# Shruthi-Analog-LP2Delay-v02.net
KiCad netlist of a schematic drawn in EAGLE
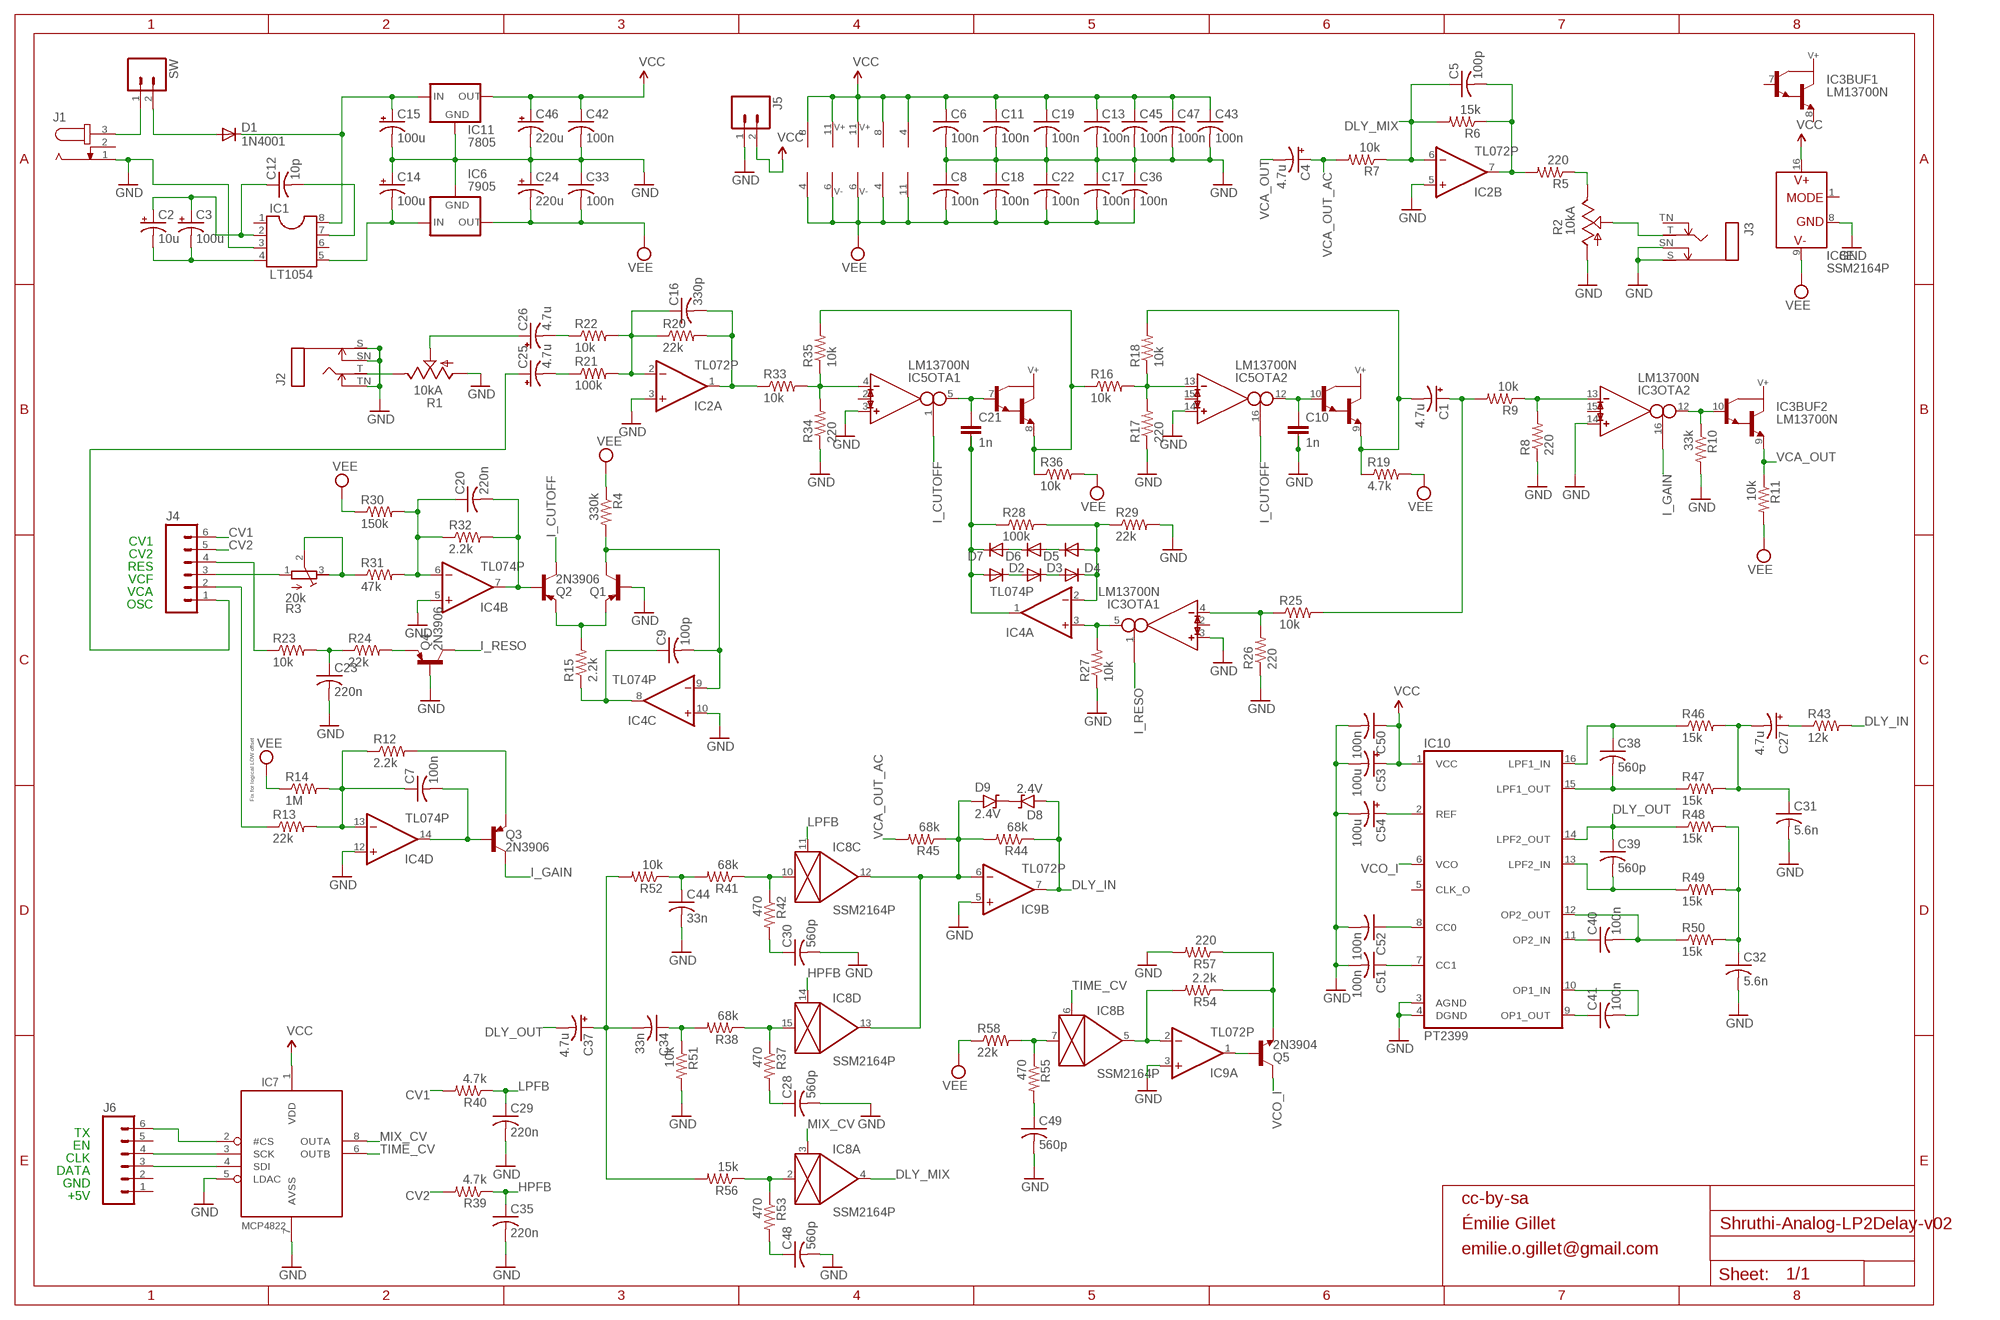
[diagram p0: schematic, sheet 1]

(export (version "E")
  (design (tool "Eeschema 10.0.6"))
  (components
    (comp (ref "C1")
      (value "4.7u")
      (footprint "eagle-import:E2,5-6")
      (libsource (lib "eagle-import") (part "CPOL-USE2.5-6"))
    )
    (comp (ref "C2")
      (value "10u")
      (footprint "eagle-import:E2,5-5")
      (libsource (lib "eagle-import") (part "CPOL-USE2.5-5"))
    )
    (comp (ref "C3")
      (value "100u")
      (footprint "eagle-import:E2,5-6")
      (libsource (lib "eagle-import") (part "CPOL-USE2.5-6"))
    )
    (comp (ref "C4")
      (value "4.7u")
      (footprint "eagle-import:E2,5-6")
      (libsource (lib "eagle-import") (part "CPOL-USE2.5-6"))
    )
    (comp (ref "C5")
      (value "100p")
      (footprint "eagle-import:C025-025X050")
      (libsource (lib "eagle-import") (part "C-US025-025X050"))
    )
    (comp (ref "C6")
      (value "100n")
      (footprint "eagle-import:C025-025X050")
      (libsource (lib "eagle-import") (part "C-US025-025X050"))
    )
    (comp (ref "C7")
      (value "100n")
      (footprint "eagle-import:C025-025X050")
      (libsource (lib "eagle-import") (part "C-US025-025X050"))
    )
    (comp (ref "C8")
      (value "100n")
      (footprint "eagle-import:C025-025X050")
      (libsource (lib "eagle-import") (part "C-US025-025X050"))
    )
    (comp (ref "C9")
      (value "100p")
      (footprint "eagle-import:C025-025X050")
      (libsource (lib "eagle-import") (part "C-US025-025X050"))
    )
    (comp (ref "C10")
      (value "1n")
      (footprint "eagle-import:C2.5_5-2")
      (libsource (lib "eagle-import") (part "C-2.5-5/2"))
    )
    (comp (ref "C11")
      (value "100n")
      (footprint "eagle-import:C025-025X050")
      (libsource (lib "eagle-import") (part "C-US025-025X050"))
    )
    (comp (ref "C12")
      (value "10p")
      (footprint "eagle-import:C025-025X050")
      (libsource (lib "eagle-import") (part "C-US025-025X050"))
    )
    (comp (ref "C13")
      (value "100n")
      (footprint "eagle-import:C025-025X050")
      (libsource (lib "eagle-import") (part "C-US025-025X050"))
    )
    (comp (ref "C14")
      (value "100u")
      (footprint "eagle-import:E2,5-7")
      (libsource (lib "eagle-import") (part "CPOL-USE2.5-7"))
    )
    (comp (ref "C15")
      (value "100u")
      (footprint "eagle-import:E2,5-7")
      (libsource (lib "eagle-import") (part "CPOL-USE2.5-7"))
    )
    (comp (ref "C16")
      (value "330p")
      (footprint "eagle-import:C025-025X050")
      (libsource (lib "eagle-import") (part "C-US025-025X050"))
    )
    (comp (ref "C17")
      (value "100n")
      (footprint "eagle-import:C025-025X050")
      (libsource (lib "eagle-import") (part "C-US025-025X050"))
    )
    (comp (ref "C18")
      (value "100n")
      (footprint "eagle-import:C025-025X050")
      (libsource (lib "eagle-import") (part "C-US025-025X050"))
    )
    (comp (ref "C19")
      (value "100n")
      (footprint "eagle-import:C025-025X050")
      (libsource (lib "eagle-import") (part "C-US025-025X050"))
    )
    (comp (ref "C20")
      (value "220n")
      (footprint "eagle-import:C025-025X050")
      (libsource (lib "eagle-import") (part "C-US025-025X050"))
    )
    (comp (ref "C21")
      (value "1n")
      (footprint "eagle-import:C2.5_5-2")
      (libsource (lib "eagle-import") (part "C-2.5-5/2"))
    )
    (comp (ref "C22")
      (value "100n")
      (footprint "eagle-import:C025-025X050")
      (libsource (lib "eagle-import") (part "C-US025-025X050"))
    )
    (comp (ref "C23")
      (value "220n")
      (footprint "eagle-import:C025-025X050")
      (libsource (lib "eagle-import") (part "C-US025-025X050"))
    )
    (comp (ref "C24")
      (value "220u")
      (footprint "eagle-import:E5-10,5")
      (libsource (lib "eagle-import") (part "CPOL-USE5-10.5"))
    )
    (comp (ref "C25")
      (value "4.7u")
      (footprint "eagle-import:E2,5-6")
      (libsource (lib "eagle-import") (part "CPOL-USE2.5-6"))
    )
    (comp (ref "C26")
      (value "4.7u")
      (footprint "eagle-import:E2,5-6")
      (libsource (lib "eagle-import") (part "CPOL-USE2.5-6"))
    )
    (comp (ref "C27")
      (value "4.7u")
      (footprint "eagle-import:E2,5-6")
      (libsource (lib "eagle-import") (part "CPOL-USE2.5-6"))
    )
    (comp (ref "C28")
      (value "560p")
      (footprint "eagle-import:C025-025X050")
      (libsource (lib "eagle-import") (part "C-US025-025X050"))
    )
    (comp (ref "C29")
      (value "220n")
      (footprint "eagle-import:C025-025X050")
      (libsource (lib "eagle-import") (part "C-US025-025X050"))
    )
    (comp (ref "C30")
      (value "560p")
      (footprint "eagle-import:C025-025X050")
      (libsource (lib "eagle-import") (part "C-US025-025X050"))
    )
    (comp (ref "C31")
      (value "5.6n")
      (footprint "eagle-import:C025-025X050")
      (libsource (lib "eagle-import") (part "C-US025-025X050"))
    )
    (comp (ref "C32")
      (value "5.6n")
      (footprint "eagle-import:C025-025X050")
      (libsource (lib "eagle-import") (part "C-US025-025X050"))
    )
    (comp (ref "C33")
      (value "100n")
      (footprint "eagle-import:C025-025X050")
      (libsource (lib "eagle-import") (part "C-US025-025X050"))
    )
    (comp (ref "C34")
      (value "33n")
      (footprint "eagle-import:C050-025X075")
      (libsource (lib "eagle-import") (part "C-US050-025X075"))
    )
    (comp (ref "C35")
      (value "220n")
      (footprint "eagle-import:C025-025X050")
      (libsource (lib "eagle-import") (part "C-US025-025X050"))
    )
    (comp (ref "C36")
      (value "100n")
      (footprint "eagle-import:C025-025X050")
      (libsource (lib "eagle-import") (part "C-US025-025X050"))
    )
    (comp (ref "C37")
      (value "4.7u")
      (footprint "eagle-import:E2,5-6")
      (libsource (lib "eagle-import") (part "CPOL-USE2.5-6"))
    )
    (comp (ref "C38")
      (value "560p")
      (footprint "eagle-import:C025-025X050")
      (libsource (lib "eagle-import") (part "C-US025-025X050"))
    )
    (comp (ref "C39")
      (value "560p")
      (footprint "eagle-import:C025-025X050")
      (libsource (lib "eagle-import") (part "C-US025-025X050"))
    )
    (comp (ref "C40")
      (value "100n")
      (footprint "eagle-import:C025-025X050")
      (libsource (lib "eagle-import") (part "C-US025-025X050"))
    )
    (comp (ref "C41")
      (value "100n")
      (footprint "eagle-import:C025-025X050")
      (libsource (lib "eagle-import") (part "C-US025-025X050"))
    )
    (comp (ref "C42")
      (value "100n")
      (footprint "eagle-import:C025-025X050")
      (libsource (lib "eagle-import") (part "C-US025-025X050"))
    )
    (comp (ref "C43")
      (value "100n")
      (footprint "eagle-import:C025-025X050")
      (libsource (lib "eagle-import") (part "C-US025-025X050"))
    )
    (comp (ref "C44")
      (value "33n")
      (footprint "eagle-import:C050-025X075")
      (libsource (lib "eagle-import") (part "C-US050-025X075"))
    )
    (comp (ref "C45")
      (value "100n")
      (footprint "eagle-import:C025-025X050")
      (libsource (lib "eagle-import") (part "C-US025-025X050"))
    )
    (comp (ref "C46")
      (value "220u")
      (footprint "eagle-import:E5-10,5")
      (libsource (lib "eagle-import") (part "CPOL-USE5-10.5"))
    )
    (comp (ref "C47")
      (value "100n")
      (footprint "eagle-import:C025-025X050")
      (libsource (lib "eagle-import") (part "C-US025-025X050"))
    )
    (comp (ref "C48")
      (value "560p")
      (footprint "eagle-import:C025-025X050")
      (libsource (lib "eagle-import") (part "C-US025-025X050"))
    )
    (comp (ref "C49")
      (value "560p")
      (footprint "eagle-import:C025-025X050")
      (libsource (lib "eagle-import") (part "C-US025-025X050"))
    )
    (comp (ref "C50")
      (value "100n")
      (footprint "eagle-import:C025-025X050")
      (libsource (lib "eagle-import") (part "C-US025-025X050"))
    )
    (comp (ref "C51")
      (value "100n")
      (footprint "eagle-import:C025-025X050")
      (libsource (lib "eagle-import") (part "C-US025-025X050"))
    )
    (comp (ref "C52")
      (value "100n")
      (footprint "eagle-import:C025-025X050")
      (libsource (lib "eagle-import") (part "C-US025-025X050"))
    )
    (comp (ref "C53")
      (value "100u")
      (footprint "eagle-import:E2,5-7")
      (libsource (lib "eagle-import") (part "CPOL-USE2.5-7"))
    )
    (comp (ref "C54")
      (value "100u")
      (footprint "eagle-import:E2,5-7")
      (libsource (lib "eagle-import") (part "CPOL-USE2.5-7"))
    )
    (comp (ref "D1")
      (value "1N4001")
      (footprint "eagle-import:DO41-10")
      (libsource (lib "eagle-import") (part "1N4004"))
    )
    (comp (ref "D2")
      (value "DIODE-D-5")
      (footprint "eagle-import:D-5")
      (libsource (lib "eagle-import") (part "DIODE-D-5"))
    )
    (comp (ref "D3")
      (value "DIODE-D-5")
      (footprint "eagle-import:D-5")
      (libsource (lib "eagle-import") (part "DIODE-D-5"))
    )
    (comp (ref "D4")
      (value "DIODE-D-5")
      (footprint "eagle-import:D-5")
      (libsource (lib "eagle-import") (part "DIODE-D-5"))
    )
    (comp (ref "D5")
      (value "DIODE-D-5")
      (footprint "eagle-import:D-5")
      (libsource (lib "eagle-import") (part "DIODE-D-5"))
    )
    (comp (ref "D6")
      (value "DIODE-D-5")
      (footprint "eagle-import:D-5")
      (libsource (lib "eagle-import") (part "DIODE-D-5"))
    )
    (comp (ref "D7")
      (value "DIODE-D-5")
      (footprint "eagle-import:D-5")
      (libsource (lib "eagle-import") (part "DIODE-D-5"))
    )
    (comp (ref "D8")
      (value "2.4V")
      (footprint "eagle-import:D-5")
      (libsource (lib "eagle-import") (part "1N47XXDO35"))
    )
    (comp (ref "D9")
      (value "2.4V")
      (footprint "eagle-import:D-5")
      (libsource (lib "eagle-import") (part "1N47XXDO35"))
    )
    (comp (ref "IC1")
      (value "LT1054")
      (footprint "eagle-import:DIL08")
      (libsource (lib "eagle-import") (part "DIL8"))
    )
    (comp (ref "IC2")
      (value "TL072P")
      (footprint "eagle-import:DIL08")
      (libsource (lib "eagle-import") (part "TL072P"))
    )
    (comp (ref "IC3")
      (value "LM13700N")
      (footprint "eagle-import:DIL16")
      (libsource (lib "eagle-import") (part "LM13700N"))
    )
    (comp (ref "IC4")
      (value "TL074P")
      (footprint "eagle-import:DIL14")
      (libsource (lib "eagle-import") (part "TL084P"))
    )
    (comp (ref "IC5")
      (value "LM13700N")
      (footprint "eagle-import:DIL16")
      (libsource (lib "eagle-import") (part "LM13700N"))
    )
    (comp (ref "IC6")
      (value "7905")
      (footprint "eagle-import:79XXS")
      (libsource (lib "eagle-import") (part "79XXS"))
    )
    (comp (ref "IC7")
      (value "MCP4822")
      (footprint "eagle-import:DIL08")
      (libsource (lib "eagle-import") (part "MCP4822"))
    )
    (comp (ref "IC8")
      (value "SSM2164P")
      (footprint "eagle-import:DIL16")
      (libsource (lib "eagle-import") (part "SSM2164P"))
    )
    (comp (ref "IC9")
      (value "TL072P")
      (footprint "eagle-import:DIL08")
      (libsource (lib "eagle-import") (part "TL072P"))
    )
    (comp (ref "IC10")
      (value "PT2399")
      (footprint "eagle-import:DIL16")
      (libsource (lib "eagle-import") (part "PT2399"))
    )
    (comp (ref "IC11")
      (value "7805")
      (footprint "eagle-import:78XXS")
      (libsource (lib "eagle-import") (part "78XXS"))
    )
    (comp (ref "J1")
      (value "JACK-PLUG2")
      (footprint "eagle-import:SPC4078_BIG_HOLES")
      (libsource (lib "eagle-import") (part "JACK-PLUG2"))
    )
    (comp (ref "J2")
      (value "MONOSWS")
      (footprint "eagle-import:NMJ4HC-S")
      (libsource (lib "eagle-import") (part "MONOSWS"))
    )
    (comp (ref "J3")
      (value "MONOSWS")
      (footprint "eagle-import:NMJ4HC-S")
      (libsource (lib "eagle-import") (part "MONOSWS"))
    )
    (comp (ref "J4")
      (value "M06SIP")
      (footprint "eagle-import:1X06")
      (libsource (lib "eagle-import") (part "M06SIP"))
    )
    (comp (ref "J5")
      (value "M02PTH")
      (footprint "eagle-import:1X02")
      (libsource (lib "eagle-import") (part "M02PTH"))
    )
    (comp (ref "J6")
      (value "M06SIP")
      (footprint "eagle-import:1X06")
      (libsource (lib "eagle-import") (part "M06SIP"))
    )
    (comp (ref "Q1")
      (value "2N3906")
      (footprint "eagle-import:TO92-")
      (libsource (lib "eagle-import") (part "2N3906-"))
    )
    (comp (ref "Q2")
      (value "2N3906")
      (footprint "eagle-import:TO92-")
      (libsource (lib "eagle-import") (part "2N3906-"))
    )
    (comp (ref "Q3")
      (value "2N3906")
      (footprint "eagle-import:TO92-")
      (libsource (lib "eagle-import") (part "2N3906-"))
    )
    (comp (ref "Q4")
      (value "2N3906")
      (footprint "eagle-import:TO92-")
      (libsource (lib "eagle-import") (part "2N3906-"))
    )
    (comp (ref "Q5")
      (value "2N3904")
      (footprint "eagle-import:TO92-")
      (libsource (lib "eagle-import") (part "2N3904"))
    )
    (comp (ref "R1")
      (value "10kA")
      (footprint "eagle-import:CABLE_POT_6MM")
      (libsource (lib "eagle-import") (part "POT_USCABLED"))
    )
    (comp (ref "R2")
      (value "10kA")
      (footprint "eagle-import:CABLE_POT_6MM")
      (libsource (lib "eagle-import") (part "POT_USCABLED"))
    )
    (comp (ref "R3")
      (value "20k")
      (footprint "eagle-import:RTRIM3296X")
      (libsource (lib "eagle-import") (part "R-TRIMM3296X"))
    )
    (comp (ref "R4")
      (value "330k")
      (footprint "eagle-import:0204_7")
      (libsource (lib "eagle-import") (part "R-US_0204/7"))
    )
    (comp (ref "R5")
      (value "220")
      (footprint "eagle-import:0204_7")
      (libsource (lib "eagle-import") (part "R-US_0204/7"))
    )
    (comp (ref "R6")
      (value "15k")
      (footprint "eagle-import:0204_7")
      (libsource (lib "eagle-import") (part "R-US_0204/7"))
    )
    (comp (ref "R7")
      (value "10k")
      (footprint "eagle-import:0204_7")
      (libsource (lib "eagle-import") (part "R-US_0204/7"))
    )
    (comp (ref "R8")
      (value "220")
      (footprint "eagle-import:0204_7")
      (libsource (lib "eagle-import") (part "R-US_0204/7"))
    )
    (comp (ref "R9")
      (value "10k")
      (footprint "eagle-import:0204_7")
      (libsource (lib "eagle-import") (part "R-US_0204/7"))
    )
    (comp (ref "R10")
      (value "33k")
      (footprint "eagle-import:0204_7")
      (libsource (lib "eagle-import") (part "R-US_0204/7"))
    )
    (comp (ref "R11")
      (value "10k")
      (footprint "eagle-import:0204_7")
      (libsource (lib "eagle-import") (part "R-US_0204/7"))
    )
    (comp (ref "R12")
      (value "2.2k")
      (footprint "eagle-import:0204_7")
      (libsource (lib "eagle-import") (part "R-US_0204/7"))
    )
    (comp (ref "R13")
      (value "22k")
      (footprint "eagle-import:0204_7")
      (libsource (lib "eagle-import") (part "R-US_0204/7"))
    )
    (comp (ref "R14")
      (value "1M")
      (footprint "eagle-import:0204_7")
      (libsource (lib "eagle-import") (part "R-US_0204/7"))
    )
    (comp (ref "R15")
      (value "2.2k")
      (footprint "eagle-import:0204_7")
      (libsource (lib "eagle-import") (part "R-US_0204/7"))
    )
    (comp (ref "R16")
      (value "10k")
      (footprint "eagle-import:0204_7")
      (libsource (lib "eagle-import") (part "R-US_0204/7"))
    )
    (comp (ref "R17")
      (value "220")
      (footprint "eagle-import:0204_7")
      (libsource (lib "eagle-import") (part "R-US_0204/7"))
    )
    (comp (ref "R18")
      (value "10k")
      (footprint "eagle-import:0204_7")
      (libsource (lib "eagle-import") (part "R-US_0204/7"))
    )
    (comp (ref "R19")
      (value "4.7k")
      (footprint "eagle-import:0204_7")
      (libsource (lib "eagle-import") (part "R-US_0204/7"))
    )
    (comp (ref "R20")
      (value "22k")
      (footprint "eagle-import:0204_7")
      (libsource (lib "eagle-import") (part "R-US_0204/7"))
    )
    (comp (ref "R21")
      (value "100k")
      (footprint "eagle-import:0204_7")
      (libsource (lib "eagle-import") (part "R-US_0204/7"))
    )
    (comp (ref "R22")
      (value "10k")
      (footprint "eagle-import:0204_7")
      (libsource (lib "eagle-import") (part "R-US_0204/7"))
    )
    (comp (ref "R23")
      (value "10k")
      (footprint "eagle-import:0204_7")
      (libsource (lib "eagle-import") (part "R-US_0204/7"))
    )
    (comp (ref "R24")
      (value "22k")
      (footprint "eagle-import:0204_7")
      (libsource (lib "eagle-import") (part "R-US_0204/7"))
    )
    (comp (ref "R25")
      (value "10k")
      (footprint "eagle-import:0204_7")
      (libsource (lib "eagle-import") (part "R-US_0204/7"))
    )
    (comp (ref "R26")
      (value "220")
      (footprint "eagle-import:0204_7")
      (libsource (lib "eagle-import") (part "R-US_0204/7"))
    )
    (comp (ref "R27")
      (value "10k")
      (footprint "eagle-import:0204_7")
      (libsource (lib "eagle-import") (part "R-US_0204/7"))
    )
    (comp (ref "R28")
      (value "100k")
      (footprint "eagle-import:0204_7")
      (libsource (lib "eagle-import") (part "R-US_0204/7"))
    )
    (comp (ref "R29")
      (value "22k")
      (footprint "eagle-import:0204_7")
      (libsource (lib "eagle-import") (part "R-US_0204/7"))
    )
    (comp (ref "R30")
      (value "150k")
      (footprint "eagle-import:0204_7")
      (libsource (lib "eagle-import") (part "R-US_0204/7"))
    )
    (comp (ref "R31")
      (value "47k")
      (footprint "eagle-import:0204_7")
      (libsource (lib "eagle-import") (part "R-US_0204/7"))
    )
    (comp (ref "R32")
      (value "2.2k")
      (footprint "eagle-import:0204_7")
      (libsource (lib "eagle-import") (part "R-US_0204/7"))
    )
    (comp (ref "R33")
      (value "10k")
      (footprint "eagle-import:0204_7")
      (libsource (lib "eagle-import") (part "R-US_0204/7"))
    )
    (comp (ref "R34")
      (value "220")
      (footprint "eagle-import:0204_7")
      (libsource (lib "eagle-import") (part "R-US_0204/7"))
    )
    (comp (ref "R35")
      (value "10k")
      (footprint "eagle-import:0204_7")
      (libsource (lib "eagle-import") (part "R-US_0204/7"))
    )
    (comp (ref "R36")
      (value "10k")
      (footprint "eagle-import:0204_7")
      (libsource (lib "eagle-import") (part "R-US_0204/7"))
    )
    (comp (ref "R37")
      (value "470")
      (footprint "eagle-import:0204_7")
      (libsource (lib "eagle-import") (part "R-US_0204/7"))
    )
    (comp (ref "R38")
      (value "68k")
      (footprint "eagle-import:0204_7")
      (libsource (lib "eagle-import") (part "R-US_0204/7"))
    )
    (comp (ref "R39")
      (value "4.7k")
      (footprint "eagle-import:0204_7")
      (libsource (lib "eagle-import") (part "R-US_0204/7"))
    )
    (comp (ref "R40")
      (value "4.7k")
      (footprint "eagle-import:0204_7")
      (libsource (lib "eagle-import") (part "R-US_0204/7"))
    )
    (comp (ref "R41")
      (value "68k")
      (footprint "eagle-import:0204_7")
      (libsource (lib "eagle-import") (part "R-US_0204/7"))
    )
    (comp (ref "R42")
      (value "470")
      (footprint "eagle-import:0204_7")
      (libsource (lib "eagle-import") (part "R-US_0204/7"))
    )
    (comp (ref "R43")
      (value "12k")
      (footprint "eagle-import:0204_7")
      (libsource (lib "eagle-import") (part "R-US_0204/7"))
    )
    (comp (ref "R44")
      (value "68k")
      (footprint "eagle-import:0204_7")
      (libsource (lib "eagle-import") (part "R-US_0204/7"))
    )
    (comp (ref "R45")
      (value "68k")
      (footprint "eagle-import:0204_7")
      (libsource (lib "eagle-import") (part "R-US_0204/7"))
    )
    (comp (ref "R46")
      (value "15k")
      (footprint "eagle-import:0204_7")
      (libsource (lib "eagle-import") (part "R-US_0204/7"))
    )
    (comp (ref "R47")
      (value "15k")
      (footprint "eagle-import:0204_7")
      (libsource (lib "eagle-import") (part "R-US_0204/7"))
    )
    (comp (ref "R48")
      (value "15k")
      (footprint "eagle-import:0204_7")
      (libsource (lib "eagle-import") (part "R-US_0204/7"))
    )
    (comp (ref "R49")
      (value "15k")
      (footprint "eagle-import:0204_7")
      (libsource (lib "eagle-import") (part "R-US_0204/7"))
    )
    (comp (ref "R50")
      (value "15k")
      (footprint "eagle-import:0204_7")
      (libsource (lib "eagle-import") (part "R-US_0204/7"))
    )
    (comp (ref "R51")
      (value "10k")
      (footprint "eagle-import:0204_7")
      (libsource (lib "eagle-import") (part "R-US_0204/7"))
    )
    (comp (ref "R52")
      (value "10k")
      (footprint "eagle-import:0204_7")
      (libsource (lib "eagle-import") (part "R-US_0204/7"))
    )
    (comp (ref "R53")
      (value "470")
      (footprint "eagle-import:0204_7")
      (libsource (lib "eagle-import") (part "R-US_0204/7"))
    )
    (comp (ref "R54")
      (value "2.2k")
      (footprint "eagle-import:0204_7")
      (libsource (lib "eagle-import") (part "R-US_0204/7"))
    )
    (comp (ref "R55")
      (value "470")
      (footprint "eagle-import:0204_7")
      (libsource (lib "eagle-import") (part "R-US_0204/7"))
    )
    (comp (ref "R56")
      (value "15k")
      (footprint "eagle-import:0204_7")
      (libsource (lib "eagle-import") (part "R-US_0204/7"))
    )
    (comp (ref "R57")
      (value "220")
      (footprint "eagle-import:0204_7")
      (libsource (lib "eagle-import") (part "R-US_0204/7"))
    )
    (comp (ref "R58")
      (value "22k")
      (footprint "eagle-import:0204_7")
      (libsource (lib "eagle-import") (part "R-US_0204/7"))
    )
    (comp (ref "SW")
      (value "M02PTH")
      (footprint "eagle-import:1X02")
      (libsource (lib "eagle-import") (part "M02PTH"))
    )
  )
  (nets
    (net (code "1") (name "/CV1") (class "Default")
      (node (ref "J4") (pin "6") (pinfunction "6_6") (pintype "passive"))
      (node (ref "R40") (pin "2") (pinfunction "2_2") (pintype "passive"))
    )
    (net (code "2") (name "/CV2") (class "Default")
      (node (ref "J4") (pin "5") (pinfunction "5_5") (pintype "passive"))
      (node (ref "R39") (pin "2") (pinfunction "2_2") (pintype "passive"))
    )
    (net (code "3") (name "/DLY_IN") (class "Default")
      (node (ref "D8") (pin "A") (pinfunction "A_A") (pintype "passive"))
      (node (ref "IC9") (pin "7") (pinfunction "OUT_7") (pintype "output"))
      (node (ref "R43") (pin "2") (pinfunction "2_2") (pintype "passive"))
      (node (ref "R44") (pin "1") (pinfunction "1_1") (pintype "passive"))
    )
    (net (code "4") (name "/DLY_MIX") (class "Default")
      (node (ref "C5") (pin "1") (pinfunction "1_1") (pintype "passive"))
      (node (ref "IC2") (pin "6") (pinfunction "-IN_6") (pintype "input"))
      (node (ref "IC8") (pin "4") (pinfunction "OUT_4") (pintype "output"))
      (node (ref "R6") (pin "2") (pinfunction "2_2") (pintype "passive"))
      (node (ref "R7") (pin "1") (pinfunction "1_1") (pintype "passive"))
    )
    (net (code "5") (name "/DLY_OUT") (class "Default")
      (node (ref "C37") (pin "-") (pinfunction "-_-") (pintype "passive"))
      (node (ref "C39") (pin "1") (pinfunction "1_1") (pintype "passive"))
      (node (ref "IC10") (pin "14") (pinfunction "LPF2_OUT_14") (pintype "input"))
      (node (ref "R48") (pin "1") (pinfunction "1_1") (pintype "passive"))
    )
    (net (code "6") (name "/HPFB") (class "Default")
      (node (ref "C35") (pin "1") (pinfunction "1_1") (pintype "passive"))
      (node (ref "IC8") (pin "14") (pinfunction "CTRL_14") (pintype "input"))
      (node (ref "R39") (pin "1") (pinfunction "1_1") (pintype "passive"))
    )
    (net (code "7") (name "/I_CUTOFF") (class "Default")
      (node (ref "IC5") (pin "1") (pinfunction "I_BIAS_1") (pintype "input"))
      (node (ref "IC5") (pin "16") (pinfunction "I_BIAS_16") (pintype "input"))
      (node (ref "Q2") (pin "1") (pinfunction "C_1") (pintype "passive"))
    )
    (net (code "8") (name "/I_GAIN") (class "Default")
      (node (ref "IC3") (pin "16") (pinfunction "I_BIAS_16") (pintype "input"))
      (node (ref "Q3") (pin "1") (pinfunction "C_1") (pintype "passive"))
    )
    (net (code "9") (name "/I_RESO") (class "Default")
      (node (ref "IC3") (pin "1") (pinfunction "I_BIAS_1") (pintype "input"))
      (node (ref "Q4") (pin "1") (pinfunction "C_1") (pintype "passive"))
    )
    (net (code "10") (name "/LPFB") (class "Default")
      (node (ref "C29") (pin "1") (pinfunction "1_1") (pintype "passive"))
      (node (ref "IC8") (pin "11") (pinfunction "CTRL_11") (pintype "input"))
      (node (ref "R40") (pin "1") (pinfunction "1_1") (pintype "passive"))
    )
    (net (code "11") (name "/MIX_CV") (class "Default")
      (node (ref "IC7") (pin "8") (pinfunction "OUTA_8") (pintype "output"))
      (node (ref "IC8") (pin "3") (pinfunction "CTRL_3") (pintype "input"))
    )
    (net (code "12") (name "/TIME_CV") (class "Default")
      (node (ref "IC7") (pin "6") (pinfunction "OUTB_6") (pintype "output"))
      (node (ref "IC8") (pin "6") (pinfunction "CTRL_6") (pintype "input"))
    )
    (net (code "13") (name "/VCA_OUT") (class "Default")
      (node (ref "C4") (pin "-") (pinfunction "-_-") (pintype "passive"))
      (node (ref "IC3") (pin "9") (pinfunction "E_9") (pintype "passive"))
      (node (ref "R11") (pin "1") (pinfunction "1_1") (pintype "passive"))
    )
    (net (code "14") (name "/VCA_OUT_AC") (class "Default")
      (node (ref "C4") (pin "+") (pinfunction "+_+") (pintype "passive"))
      (node (ref "R45") (pin "2") (pinfunction "2_2") (pintype "passive"))
      (node (ref "R7") (pin "2") (pinfunction "2_2") (pintype "passive"))
    )
    (net (code "15") (name "/VCO_I") (class "Default")
      (node (ref "IC10") (pin "6") (pinfunction "VCO_6") (pintype "input"))
      (node (ref "Q5") (pin "1") (pinfunction "C_1") (pintype "passive"))
    )
    (net (code "16") (name "GND") (class "Default")
      (node (ref "C10") (pin "2") (pinfunction "2_2") (pintype "passive"))
      (node (ref "C10") (pin "3") (pinfunction "3_3") (pintype "passive"))
      (node (ref "C11") (pin "2") (pinfunction "2_2") (pintype "passive"))
      (node (ref "C13") (pin "2") (pinfunction "2_2") (pintype "passive"))
      (node (ref "C14") (pin "+") (pinfunction "+_+") (pintype "passive"))
      (node (ref "C15") (pin "-") (pinfunction "-_-") (pintype "passive"))
      (node (ref "C17") (pin "1") (pinfunction "1_1") (pintype "passive"))
      (node (ref "C18") (pin "1") (pinfunction "1_1") (pintype "passive"))
      (node (ref "C19") (pin "2") (pinfunction "2_2") (pintype "passive"))
      (node (ref "C22") (pin "1") (pinfunction "1_1") (pintype "passive"))
      (node (ref "C23") (pin "2") (pinfunction "2_2") (pintype "passive"))
      (node (ref "C24") (pin "+") (pinfunction "+_+") (pintype "passive"))
      (node (ref "C28") (pin "2") (pinfunction "2_2") (pintype "passive"))
      (node (ref "C29") (pin "2") (pinfunction "2_2") (pintype "passive"))
      (node (ref "C30") (pin "2") (pinfunction "2_2") (pintype "passive"))
      (node (ref "C31") (pin "2") (pinfunction "2_2") (pintype "passive"))
      (node (ref "C32") (pin "2") (pinfunction "2_2") (pintype "passive"))
      (node (ref "C33") (pin "1") (pinfunction "1_1") (pintype "passive"))
      (node (ref "C35") (pin "2") (pinfunction "2_2") (pintype "passive"))
      (node (ref "C36") (pin "1") (pinfunction "1_1") (pintype "passive"))
      (node (ref "C42") (pin "2") (pinfunction "2_2") (pintype "passive"))
      (node (ref "C43") (pin "2") (pinfunction "2_2") (pintype "passive"))
      (node (ref "C44") (pin "2") (pinfunction "2_2") (pintype "passive"))
      (node (ref "C45") (pin "2") (pinfunction "2_2") (pintype "passive"))
      (node (ref "C46") (pin "-") (pinfunction "-_-") (pintype "passive"))
      (node (ref "C47") (pin "2") (pinfunction "2_2") (pintype "passive"))
      (node (ref "C48") (pin "2") (pinfunction "2_2") (pintype "passive"))
      (node (ref "C49") (pin "2") (pinfunction "2_2") (pintype "passive"))
      (node (ref "C50") (pin "2") (pinfunction "2_2") (pintype "passive"))
      (node (ref "C51") (pin "2") (pinfunction "2_2") (pintype "passive"))
      (node (ref "C52") (pin "2") (pinfunction "2_2") (pintype "passive"))
      (node (ref "C53") (pin "-") (pinfunction "-_-") (pintype "passive"))
      (node (ref "C54") (pin "-") (pinfunction "-_-") (pintype "passive"))
      (node (ref "C6") (pin "2") (pinfunction "2_2") (pintype "passive"))
      (node (ref "C8") (pin "1") (pinfunction "1_1") (pintype "passive"))
      (node (ref "IC1") (pin "3") (pinfunction "3_3") (pintype "passive"))
      (node (ref "IC10") (pin "3") (pinfunction "AGND_3") (pintype "input"))
      (node (ref "IC10") (pin "4") (pinfunction "DGND_4") (pintype "input"))
      (node (ref "IC11") (pin "GND") (pinfunction "GND_GND") (pintype "input"))
      (node (ref "IC2") (pin "3") (pinfunction "+IN_3") (pintype "input"))
      (node (ref "IC2") (pin "5") (pinfunction "+IN_5") (pintype "input"))
      (node (ref "IC3") (pin "14") (pinfunction "IN_P_14") (pintype "input"))
      (node (ref "IC3") (pin "3") (pinfunction "IN_P_3") (pintype "input"))
      (node (ref "IC4") (pin "10") (pinfunction "+IN_10") (pintype "input"))
      (node (ref "IC4") (pin "12") (pinfunction "+IN_12") (pintype "input"))
      (node (ref "IC4") (pin "5") (pinfunction "+IN_5") (pintype "input"))
      (node (ref "IC5") (pin "14") (pinfunction "IN_P_14") (pintype "input"))
      (node (ref "IC5") (pin "3") (pinfunction "IN_P_3") (pintype "input"))
      (node (ref "IC6") (pin "GND") (pinfunction "GND_GND") (pintype "input"))
      (node (ref "IC7") (pin "5") (pinfunction "LDAC_5") (pintype "input"))
      (node (ref "IC7") (pin "7") (pinfunction "AVSS_7") (pintype "power_in"))
      (node (ref "IC8") (pin "8") (pinfunction "GND_8") (pintype "power_in"))
      (node (ref "IC9") (pin "3") (pinfunction "+IN_3") (pintype "input"))
      (node (ref "IC9") (pin "5") (pinfunction "+IN_5") (pintype "input"))
      (node (ref "J1") (pin "1") (pinfunction "1_1") (pintype "passive"))
      (node (ref "J2") (pin "S") (pinfunction "S_S") (pintype "passive"))
      (node (ref "J2") (pin "SN") (pinfunction "SN_SN") (pintype "passive"))
      (node (ref "J2") (pin "TN") (pinfunction "TN_TN") (pintype "passive"))
      (node (ref "J3") (pin "S") (pinfunction "S_S") (pintype "passive"))
      (node (ref "J3") (pin "SN") (pinfunction "SN_SN") (pintype "passive"))
      (node (ref "J5") (pin "1") (pinfunction "1_1") (pintype "passive"))
      (node (ref "Q1") (pin "2") (pinfunction "B_2") (pintype "passive"))
      (node (ref "Q4") (pin "2") (pinfunction "B_2") (pintype "passive"))
      (node (ref "R1") (pin "A") (pinfunction "A_A") (pintype "passive"))
      (node (ref "R10") (pin "2") (pinfunction "2_2") (pintype "passive"))
      (node (ref "R17") (pin "1") (pinfunction "1_1") (pintype "passive"))
      (node (ref "R2") (pin "A") (pinfunction "A_A") (pintype "passive"))
      (node (ref "R26") (pin "1") (pinfunction "1_1") (pintype "passive"))
      (node (ref "R27") (pin "1") (pinfunction "1_1") (pintype "passive"))
      (node (ref "R29") (pin "2") (pinfunction "2_2") (pintype "passive"))
      (node (ref "R34") (pin "1") (pinfunction "1_1") (pintype "passive"))
      (node (ref "R51") (pin "2") (pinfunction "2_2") (pintype "passive"))
      (node (ref "R57") (pin "2") (pinfunction "2_2") (pintype "passive"))
      (node (ref "R8") (pin "1") (pinfunction "1_1") (pintype "passive"))
    )
    (net (code "17") (name "Net-(C1-Pad+)") (class "Default")
      (node (ref "C1") (pin "+") (pinfunction "+_+") (pintype "passive"))
      (node (ref "R25") (pin "2") (pinfunction "2_2") (pintype "passive"))
      (node (ref "R9") (pin "2") (pinfunction "2_2") (pintype "passive"))
    )
    (net (code "18") (name "Net-(C2-Pad-)") (class "Default")
      (node (ref "C2") (pin "-") (pinfunction "-_-") (pintype "passive"))
      (node (ref "C3") (pin "-") (pinfunction "-_-") (pintype "passive"))
      (node (ref "IC1") (pin "4") (pinfunction "4_4") (pintype "passive"))
    )
    (net (code "19") (name "Net-(C12-Pad1)") (class "Default")
      (node (ref "C12") (pin "1") (pinfunction "1_1") (pintype "passive"))
      (node (ref "C2") (pin "+") (pinfunction "+_+") (pintype "passive"))
      (node (ref "C3") (pin "+") (pinfunction "+_+") (pintype "passive"))
      (node (ref "IC1") (pin "2") (pinfunction "2_2") (pintype "passive"))
    )
    (net (code "20") (name "Net-(C12-Pad2)") (class "Default")
      (node (ref "C12") (pin "2") (pinfunction "2_2") (pintype "passive"))
      (node (ref "IC1") (pin "7") (pinfunction "7_7") (pintype "passive"))
    )
    (net (code "21") (name "Net-(C14-Pad-)") (class "Default")
      (node (ref "C14") (pin "-") (pinfunction "-_-") (pintype "passive"))
      (node (ref "IC1") (pin "5") (pinfunction "5_5") (pintype "passive"))
      (node (ref "IC6") (pin "IN") (pinfunction "IN_IN") (pintype "input"))
    )
    (net (code "22") (name "Net-(C15-Pad+)") (class "Default")
      (node (ref "C15") (pin "+") (pinfunction "+_+") (pintype "passive"))
      (node (ref "D1") (pin "C") (pinfunction "C_C") (pintype "passive"))
      (node (ref "IC1") (pin "8") (pinfunction "8_8") (pintype "passive"))
      (node (ref "IC11") (pin "IN") (pinfunction "IN_IN") (pintype "input"))
    )
    (net (code "23") (name "Net-(C23-Pad1)") (class "Default")
      (node (ref "C23") (pin "1") (pinfunction "1_1") (pintype "passive"))
      (node (ref "R23") (pin "2") (pinfunction "2_2") (pintype "passive"))
      (node (ref "R24") (pin "1") (pinfunction "1_1") (pintype "passive"))
    )
    (net (code "24") (name "Net-(C25-Pad+)") (class "Default")
      (node (ref "C25") (pin "+") (pinfunction "+_+") (pintype "passive"))
      (node (ref "J4") (pin "1") (pinfunction "1_1") (pintype "passive"))
    )
    (net (code "25") (name "Net-(C25-Pad-)") (class "Default")
      (node (ref "C25") (pin "-") (pinfunction "-_-") (pintype "passive"))
      (node (ref "R21") (pin "1") (pinfunction "1_1") (pintype "passive"))
    )
    (net (code "26") (name "Net-(C26-Pad+)") (class "Default")
      (node (ref "C26") (pin "+") (pinfunction "+_+") (pintype "passive"))
      (node (ref "R1") (pin "S") (pinfunction "S_S") (pintype "passive"))
    )
    (net (code "27") (name "Net-(C26-Pad-)") (class "Default")
      (node (ref "C26") (pin "-") (pinfunction "-_-") (pintype "passive"))
      (node (ref "R22") (pin "1") (pinfunction "1_1") (pintype "passive"))
    )
    (net (code "28") (name "Net-(C27-Pad+)") (class "Default")
      (node (ref "C27") (pin "+") (pinfunction "+_+") (pintype "passive"))
      (node (ref "R43") (pin "1") (pinfunction "1_1") (pintype "passive"))
    )
    (net (code "29") (name "Net-(C27-Pad-)") (class "Default")
      (node (ref "C27") (pin "-") (pinfunction "-_-") (pintype "passive"))
      (node (ref "C31") (pin "1") (pinfunction "1_1") (pintype "passive"))
      (node (ref "R46") (pin "2") (pinfunction "2_2") (pintype "passive"))
      (node (ref "R47") (pin "2") (pinfunction "2_2") (pintype "passive"))
    )
    (net (code "30") (name "Net-(C28-Pad1)") (class "Default")
      (node (ref "C28") (pin "1") (pinfunction "1_1") (pintype "passive"))
      (node (ref "R37") (pin "2") (pinfunction "2_2") (pintype "passive"))
    )
    (net (code "31") (name "Net-(C30-Pad1)") (class "Default")
      (node (ref "C30") (pin "1") (pinfunction "1_1") (pintype "passive"))
      (node (ref "R42") (pin "2") (pinfunction "2_2") (pintype "passive"))
    )
    (net (code "32") (name "Net-(C32-Pad1)") (class "Default")
      (node (ref "C32") (pin "1") (pinfunction "1_1") (pintype "passive"))
      (node (ref "R48") (pin "2") (pinfunction "2_2") (pintype "passive"))
      (node (ref "R49") (pin "2") (pinfunction "2_2") (pintype "passive"))
      (node (ref "R50") (pin "2") (pinfunction "2_2") (pintype "passive"))
    )
    (net (code "33") (name "Net-(C34-Pad1)") (class "Default")
      (node (ref "C34") (pin "1") (pinfunction "1_1") (pintype "passive"))
      (node (ref "R38") (pin "2") (pinfunction "2_2") (pintype "passive"))
      (node (ref "R51") (pin "1") (pinfunction "1_1") (pintype "passive"))
    )
    (net (code "34") (name "Net-(C34-Pad2)") (class "Default")
      (node (ref "C34") (pin "2") (pinfunction "2_2") (pintype "passive"))
      (node (ref "C37") (pin "+") (pinfunction "+_+") (pintype "passive"))
      (node (ref "R52") (pin "2") (pinfunction "2_2") (pintype "passive"))
      (node (ref "R56") (pin "2") (pinfunction "2_2") (pintype "passive"))
    )
    (net (code "35") (name "Net-(C44-Pad1)") (class "Default")
      (node (ref "C44") (pin "1") (pinfunction "1_1") (pintype "passive"))
      (node (ref "R41") (pin "2") (pinfunction "2_2") (pintype "passive"))
      (node (ref "R52") (pin "1") (pinfunction "1_1") (pintype "passive"))
    )
    (net (code "36") (name "Net-(C48-Pad1)") (class "Default")
      (node (ref "C48") (pin "1") (pinfunction "1_1") (pintype "passive"))
      (node (ref "R53") (pin "2") (pinfunction "2_2") (pintype "passive"))
    )
    (net (code "37") (name "Net-(C49-Pad1)") (class "Default")
      (node (ref "C49") (pin "1") (pinfunction "1_1") (pintype "passive"))
      (node (ref "R55") (pin "2") (pinfunction "2_2") (pintype "passive"))
    )
    (net (code "38") (name "Net-(D1-PadA)") (class "Default")
      (node (ref "D1") (pin "A") (pinfunction "A_A") (pintype "passive"))
      (node (ref "SW") (pin "2") (pinfunction "2_2") (pintype "passive"))
    )
    (net (code "39") (name "Net-(D2-PadC)") (class "Default")
      (node (ref "D2") (pin "C") (pinfunction "C_C") (pintype "passive"))
      (node (ref "D3") (pin "A") (pinfunction "A_A") (pintype "passive"))
    )
    (net (code "40") (name "Net-(D3-PadC)") (class "Default")
      (node (ref "D3") (pin "C") (pinfunction "C_C") (pintype "passive"))
      (node (ref "D4") (pin "A") (pinfunction "A_A") (pintype "passive"))
    )
    (net (code "41") (name "Net-(D5-PadC)") (class "Default")
      (node (ref "D5") (pin "C") (pinfunction "C_C") (pintype "passive"))
      (node (ref "D6") (pin "A") (pinfunction "A_A") (pintype "passive"))
    )
    (net (code "42") (name "Net-(D6-PadC)") (class "Default")
      (node (ref "D6") (pin "C") (pinfunction "C_C") (pintype "passive"))
      (node (ref "D7") (pin "A") (pinfunction "A_A") (pintype "passive"))
    )
    (net (code "43") (name "Net-(D8-PadC)") (class "Default")
      (node (ref "D8") (pin "C") (pinfunction "C_C") (pintype "passive"))
      (node (ref "D9") (pin "C") (pinfunction "C_C") (pintype "passive"))
    )
    (net (code "44") (name "Net-(IC2A--IN)") (class "Default")
      (node (ref "C16") (pin "1") (pinfunction "1_1") (pintype "passive"))
      (node (ref "IC2") (pin "2") (pinfunction "-IN_2") (pintype "input"))
      (node (ref "R20") (pin "1") (pinfunction "1_1") (pintype "passive"))
      (node (ref "R21") (pin "2") (pinfunction "2_2") (pintype "passive"))
      (node (ref "R22") (pin "2") (pinfunction "2_2") (pintype "passive"))
    )
    (net (code "45") (name "Net-(IC2A-OUT)") (class "Default")
      (node (ref "C16") (pin "2") (pinfunction "2_2") (pintype "passive"))
      (node (ref "IC2") (pin "1") (pinfunction "OUT_1") (pintype "output"))
      (node (ref "R20") (pin "2") (pinfunction "2_2") (pintype "passive"))
      (node (ref "R33") (pin "1") (pinfunction "1_1") (pintype "passive"))
    )
    (net (code "46") (name "Net-(IC2B-OUT)") (class "Default")
      (node (ref "C5") (pin "2") (pinfunction "2_2") (pintype "passive"))
      (node (ref "IC2") (pin "7") (pinfunction "OUT_7") (pintype "output"))
      (node (ref "R5") (pin "2") (pinfunction "2_2") (pintype "passive"))
      (node (ref "R6") (pin "1") (pinfunction "1_1") (pintype "passive"))
    )
    (net (code "47") (name "Net-(IC3B-B)") (class "Default")
      (node (ref "IC3") (pin "10") (pinfunction "B_10") (pintype "passive"))
      (node (ref "IC3") (pin "12") (pinfunction "OUT_12") (pintype "output"))
      (node (ref "R10") (pin "1") (pinfunction "1_1") (pintype "passive"))
    )
    (net (code "48") (name "Net-(IC3C-IN_N)") (class "Default")
      (node (ref "IC3") (pin "4") (pinfunction "IN_N_4") (pintype "input"))
      (node (ref "R25") (pin "1") (pinfunction "1_1") (pintype "passive"))
      (node (ref "R26") (pin "2") (pinfunction "2_2") (pintype "passive"))
    )
    (net (code "49") (name "Net-(IC3C-OUT)") (class "Default")
      (node (ref "IC3") (pin "5") (pinfunction "OUT_5") (pintype "output"))
      (node (ref "IC4") (pin "3") (pinfunction "+IN_3") (pintype "input"))
      (node (ref "R27") (pin "2") (pinfunction "2_2") (pintype "passive"))
    )
    (net (code "50") (name "Net-(IC3D-IN_N)") (class "Default")
      (node (ref "IC3") (pin "13") (pinfunction "IN_N_13") (pintype "input"))
      (node (ref "R8") (pin "2") (pinfunction "2_2") (pintype "passive"))
      (node (ref "R9") (pin "1") (pinfunction "1_1") (pintype "passive"))
    )
    (net (code "51") (name "Net-(IC4A--IN)") (class "Default")
      (node (ref "D4") (pin "C") (pinfunction "C_C") (pintype "passive"))
      (node (ref "D5") (pin "A") (pinfunction "A_A") (pintype "passive"))
      (node (ref "IC4") (pin "2") (pinfunction "-IN_2") (pintype "input"))
      (node (ref "R28") (pin "2") (pinfunction "2_2") (pintype "passive"))
      (node (ref "R29") (pin "1") (pinfunction "1_1") (pintype "passive"))
    )
    (net (code "52") (name "Net-(IC4A-OUT)") (class "Default")
      (node (ref "C21") (pin "2") (pinfunction "2_2") (pintype "passive"))
      (node (ref "C21") (pin "3") (pinfunction "3_3") (pintype "passive"))
      (node (ref "D2") (pin "A") (pinfunction "A_A") (pintype "passive"))
      (node (ref "D7") (pin "C") (pinfunction "C_C") (pintype "passive"))
      (node (ref "IC4") (pin "1") (pinfunction "OUT_1") (pintype "output"))
      (node (ref "R28") (pin "1") (pinfunction "1_1") (pintype "passive"))
    )
    (net (code "53") (name "Net-(IC4B--IN)") (class "Default")
      (node (ref "C20") (pin "1") (pinfunction "1_1") (pintype "passive"))
      (node (ref "IC4") (pin "6") (pinfunction "-IN_6") (pintype "input"))
      (node (ref "R30") (pin "2") (pinfunction "2_2") (pintype "passive"))
      (node (ref "R31") (pin "2") (pinfunction "2_2") (pintype "passive"))
      (node (ref "R32") (pin "1") (pinfunction "1_1") (pintype "passive"))
    )
    (net (code "54") (name "Net-(IC4B-OUT)") (class "Default")
      (node (ref "C20") (pin "2") (pinfunction "2_2") (pintype "passive"))
      (node (ref "IC4") (pin "7") (pinfunction "OUT_7") (pintype "output"))
      (node (ref "Q2") (pin "2") (pinfunction "B_2") (pintype "passive"))
      (node (ref "R32") (pin "2") (pinfunction "2_2") (pintype "passive"))
    )
    (net (code "55") (name "Net-(IC4C--IN)") (class "Default")
      (node (ref "C9") (pin "2") (pinfunction "2_2") (pintype "passive"))
      (node (ref "IC4") (pin "9") (pinfunction "-IN_9") (pintype "input"))
      (node (ref "Q1") (pin "1") (pinfunction "C_1") (pintype "passive"))
      (node (ref "R4") (pin "2") (pinfunction "2_2") (pintype "passive"))
    )
    (net (code "56") (name "Net-(IC4C-OUT)") (class "Default")
      (node (ref "C9") (pin "1") (pinfunction "1_1") (pintype "passive"))
      (node (ref "IC4") (pin "8") (pinfunction "OUT_8") (pintype "output"))
      (node (ref "R15") (pin "1") (pinfunction "1_1") (pintype "passive"))
    )
    (net (code "57") (name "Net-(IC4D--IN)") (class "Default")
      (node (ref "C7") (pin "1") (pinfunction "1_1") (pintype "passive"))
      (node (ref "IC4") (pin "13") (pinfunction "-IN_13") (pintype "input"))
      (node (ref "R12") (pin "1") (pinfunction "1_1") (pintype "passive"))
      (node (ref "R13") (pin "2") (pinfunction "2_2") (pintype "passive"))
      (node (ref "R14") (pin "2") (pinfunction "2_2") (pintype "passive"))
    )
    (net (code "58") (name "Net-(IC4D-OUT)") (class "Default")
      (node (ref "C7") (pin "2") (pinfunction "2_2") (pintype "passive"))
      (node (ref "IC4") (pin "14") (pinfunction "OUT_14") (pintype "output"))
      (node (ref "Q3") (pin "2") (pinfunction "B_2") (pintype "passive"))
    )
    (net (code "59") (name "Net-(IC5A-B)") (class "Default")
      (node (ref "C21") (pin "1") (pinfunction "1_1") (pintype "passive"))
      (node (ref "IC5") (pin "5") (pinfunction "OUT_5") (pintype "output"))
      (node (ref "IC5") (pin "7") (pinfunction "B_7") (pintype "passive"))
    )
    (net (code "60") (name "Net-(IC5A-E)") (class "Default")
      (node (ref "IC5") (pin "8") (pinfunction "E_8") (pintype "passive"))
      (node (ref "R16") (pin "1") (pinfunction "1_1") (pintype "passive"))
      (node (ref "R35") (pin "2") (pinfunction "2_2") (pintype "passive"))
      (node (ref "R36") (pin "1") (pinfunction "1_1") (pintype "passive"))
    )
    (net (code "61") (name "Net-(IC5B-B)") (class "Default")
      (node (ref "C10") (pin "1") (pinfunction "1_1") (pintype "passive"))
      (node (ref "IC5") (pin "10") (pinfunction "B_10") (pintype "passive"))
      (node (ref "IC5") (pin "12") (pinfunction "OUT_12") (pintype "output"))
    )
    (net (code "62") (name "Net-(IC5B-E)") (class "Default")
      (node (ref "C1") (pin "-") (pinfunction "-_-") (pintype "passive"))
      (node (ref "IC5") (pin "9") (pinfunction "E_9") (pintype "passive"))
      (node (ref "R18") (pin "2") (pinfunction "2_2") (pintype "passive"))
      (node (ref "R19") (pin "1") (pinfunction "1_1") (pintype "passive"))
    )
    (net (code "63") (name "Net-(IC5C-IN_N)") (class "Default")
      (node (ref "IC5") (pin "4") (pinfunction "IN_N_4") (pintype "input"))
      (node (ref "R33") (pin "2") (pinfunction "2_2") (pintype "passive"))
      (node (ref "R34") (pin "2") (pinfunction "2_2") (pintype "passive"))
      (node (ref "R35") (pin "1") (pinfunction "1_1") (pintype "passive"))
    )
    (net (code "64") (name "Net-(IC5D-IN_N)") (class "Default")
      (node (ref "IC5") (pin "13") (pinfunction "IN_N_13") (pintype "input"))
      (node (ref "R16") (pin "2") (pinfunction "2_2") (pintype "passive"))
      (node (ref "R17") (pin "2") (pinfunction "2_2") (pintype "passive"))
      (node (ref "R18") (pin "1") (pinfunction "1_1") (pintype "passive"))
    )
    (net (code "65") (name "Net-(IC7-#CS)") (class "Default")
      (node (ref "IC7") (pin "2") (pinfunction "#CS_2") (pintype "input"))
      (node (ref "J6") (pin "6") (pinfunction "6_6") (pintype "passive"))
    )
    (net (code "66") (name "Net-(IC7-SCK)") (class "Default")
      (node (ref "IC7") (pin "3") (pinfunction "SCK_3") (pintype "input"))
      (node (ref "J6") (pin "4") (pinfunction "4_4") (pintype "passive"))
    )
    (net (code "67") (name "Net-(IC7-SDI)") (class "Default")
      (node (ref "IC7") (pin "4") (pinfunction "SDI_4") (pintype "input"))
      (node (ref "J6") (pin "3") (pinfunction "3_3") (pintype "passive"))
    )
    (net (code "68") (name "Net-(IC8A-IN)") (class "Default")
      (node (ref "IC8") (pin "2") (pinfunction "IN_2") (pintype "input"))
      (node (ref "R53") (pin "1") (pinfunction "1_1") (pintype "passive"))
      (node (ref "R56") (pin "1") (pinfunction "1_1") (pintype "passive"))
    )
    (net (code "69") (name "Net-(IC8B-IN)") (class "Default")
      (node (ref "IC8") (pin "7") (pinfunction "IN_7") (pintype "input"))
      (node (ref "R55") (pin "1") (pinfunction "1_1") (pintype "passive"))
      (node (ref "R58") (pin "2") (pinfunction "2_2") (pintype "passive"))
    )
    (net (code "70") (name "Net-(IC8B-OUT)") (class "Default")
      (node (ref "IC8") (pin "5") (pinfunction "OUT_5") (pintype "output"))
      (node (ref "IC9") (pin "2") (pinfunction "-IN_2") (pintype "input"))
      (node (ref "R54") (pin "2") (pinfunction "2_2") (pintype "passive"))
    )
    (net (code "71") (name "Net-(IC8C-IN)") (class "Default")
      (node (ref "IC8") (pin "10") (pinfunction "IN_10") (pintype "input"))
      (node (ref "R41") (pin "1") (pinfunction "1_1") (pintype "passive"))
      (node (ref "R42") (pin "1") (pinfunction "1_1") (pintype "passive"))
    )
    (net (code "72") (name "Net-(IC8C-OUT)") (class "Default")
      (node (ref "D9") (pin "A") (pinfunction "A_A") (pintype "passive"))
      (node (ref "IC8") (pin "12") (pinfunction "OUT_12") (pintype "output"))
      (node (ref "IC8") (pin "13") (pinfunction "OUT_13") (pintype "output"))
      (node (ref "IC9") (pin "6") (pinfunction "-IN_6") (pintype "input"))
      (node (ref "R44") (pin "2") (pinfunction "2_2") (pintype "passive"))
      (node (ref "R45") (pin "1") (pinfunction "1_1") (pintype "passive"))
    )
    (net (code "73") (name "Net-(IC8D-IN)") (class "Default")
      (node (ref "IC8") (pin "15") (pinfunction "IN_15") (pintype "input"))
      (node (ref "R37") (pin "1") (pinfunction "1_1") (pintype "passive"))
      (node (ref "R38") (pin "1") (pinfunction "1_1") (pintype "passive"))
    )
    (net (code "74") (name "Net-(IC9A-OUT)") (class "Default")
      (node (ref "IC9") (pin "1") (pinfunction "OUT_1") (pintype "output"))
      (node (ref "Q5") (pin "2") (pinfunction "B_2") (pintype "passive"))
    )
    (net (code "75") (name "Net-(IC10-CC0)") (class "Default")
      (node (ref "C52") (pin "1") (pinfunction "1_1") (pintype "passive"))
      (node (ref "IC10") (pin "8") (pinfunction "CC0_8") (pintype "input"))
    )
    (net (code "76") (name "Net-(IC10-CC1)") (class "Default")
      (node (ref "C51") (pin "1") (pinfunction "1_1") (pintype "passive"))
      (node (ref "IC10") (pin "7") (pinfunction "CC1_7") (pintype "input"))
    )
    (net (code "77") (name "Net-(IC10-LPF1_IN)") (class "Default")
      (node (ref "C38") (pin "1") (pinfunction "1_1") (pintype "passive"))
      (node (ref "IC10") (pin "16") (pinfunction "LPF1_IN_16") (pintype "input"))
      (node (ref "R46") (pin "1") (pinfunction "1_1") (pintype "passive"))
    )
    (net (code "78") (name "Net-(IC10-LPF1_OUT)") (class "Default")
      (node (ref "C38") (pin "2") (pinfunction "2_2") (pintype "passive"))
      (node (ref "IC10") (pin "15") (pinfunction "LPF1_OUT_15") (pintype "input"))
      (node (ref "R47") (pin "1") (pinfunction "1_1") (pintype "passive"))
    )
    (net (code "79") (name "Net-(IC10-LPF2_IN)") (class "Default")
      (node (ref "C39") (pin "2") (pinfunction "2_2") (pintype "passive"))
      (node (ref "IC10") (pin "13") (pinfunction "LPF2_IN_13") (pintype "input"))
      (node (ref "R49") (pin "1") (pinfunction "1_1") (pintype "passive"))
    )
    (net (code "80") (name "Net-(IC10-OP1_IN)") (class "Default")
      (node (ref "C41") (pin "2") (pinfunction "2_2") (pintype "passive"))
      (node (ref "IC10") (pin "10") (pinfunction "OP1_IN_10") (pintype "input"))
    )
    (net (code "81") (name "Net-(IC10-OP1_OUT)") (class "Default")
      (node (ref "C41") (pin "1") (pinfunction "1_1") (pintype "passive"))
      (node (ref "IC10") (pin "9") (pinfunction "OP1_OUT_9") (pintype "input"))
    )
    (net (code "82") (name "Net-(IC10-OP2_IN)") (class "Default")
      (node (ref "C40") (pin "1") (pinfunction "1_1") (pintype "passive"))
      (node (ref "IC10") (pin "11") (pinfunction "OP2_IN_11") (pintype "input"))
    )
    (net (code "83") (name "Net-(IC10-OP2_OUT)") (class "Default")
      (node (ref "C40") (pin "2") (pinfunction "2_2") (pintype "passive"))
      (node (ref "IC10") (pin "12") (pinfunction "OP2_OUT_12") (pintype "input"))
      (node (ref "R50") (pin "1") (pinfunction "1_1") (pintype "passive"))
    )
    (net (code "84") (name "Net-(IC10-REF)") (class "Default")
      (node (ref "C54") (pin "+") (pinfunction "+_+") (pintype "passive"))
      (node (ref "IC10") (pin "2") (pinfunction "REF_2") (pintype "input"))
    )
    (net (code "85") (name "Net-(J1-Pad3)") (class "Default")
      (node (ref "J1") (pin "3") (pinfunction "3_3") (pintype "passive"))
      (node (ref "SW") (pin "1") (pinfunction "1_1") (pintype "passive"))
    )
    (net (code "86") (name "Net-(J2-PadT)") (class "Default")
      (node (ref "J2") (pin "T") (pinfunction "T_T") (pintype "passive"))
      (node (ref "R1") (pin "E") (pinfunction "E_E") (pintype "passive"))
    )
    (net (code "87") (name "Net-(J3-PadT)") (class "Default")
      (node (ref "J3") (pin "T") (pinfunction "T_T") (pintype "passive"))
      (node (ref "R2") (pin "S") (pinfunction "S_S") (pintype "passive"))
    )
    (net (code "88") (name "Net-(J4-Pad2)") (class "Default")
      (node (ref "J4") (pin "2") (pinfunction "2_2") (pintype "passive"))
      (node (ref "R13") (pin "1") (pinfunction "1_1") (pintype "passive"))
    )
    (net (code "89") (name "Net-(J4-Pad4)") (class "Default")
      (node (ref "J4") (pin "4") (pinfunction "4_4") (pintype "passive"))
      (node (ref "R23") (pin "1") (pinfunction "1_1") (pintype "passive"))
    )
    (net (code "90") (name "Net-(Q1-E)") (class "Default")
      (node (ref "Q1") (pin "3") (pinfunction "E_3") (pintype "passive"))
      (node (ref "Q2") (pin "3") (pinfunction "E_3") (pintype "passive"))
      (node (ref "R15") (pin "2") (pinfunction "2_2") (pintype "passive"))
    )
    (net (code "91") (name "Net-(Q3-E)") (class "Default")
      (node (ref "Q3") (pin "3") (pinfunction "E_3") (pintype "passive"))
      (node (ref "R12") (pin "2") (pinfunction "2_2") (pintype "passive"))
    )
    (net (code "92") (name "Net-(Q4-E)") (class "Default")
      (node (ref "Q4") (pin "3") (pinfunction "E_3") (pintype "passive"))
      (node (ref "R24") (pin "2") (pinfunction "2_2") (pintype "passive"))
    )
    (net (code "93") (name "Net-(Q5-E)") (class "Default")
      (node (ref "Q5") (pin "3") (pinfunction "E_3") (pintype "passive"))
      (node (ref "R54") (pin "1") (pinfunction "1_1") (pintype "passive"))
      (node (ref "R57") (pin "1") (pinfunction "1_1") (pintype "passive"))
    )
    (net (code "94") (name "Net-(R2-PadE)") (class "Default")
      (node (ref "R2") (pin "E") (pinfunction "E_E") (pintype "passive"))
      (node (ref "R5") (pin "1") (pinfunction "1_1") (pintype "passive"))
    )
    (net (code "95") (name "Net-(R3-A)") (class "Default")
      (node (ref "R3") (pin "2") (pinfunction "S_2") (pintype "passive"))
      (node (ref "R3") (pin "3") (pinfunction "A_3") (pintype "passive"))
      (node (ref "R31") (pin "1") (pinfunction "1_1") (pintype "passive"))
    )
    (net (code "96") (name "Net-(R3-E)") (class "Default")
      (node (ref "J4") (pin "3") (pinfunction "3_3") (pintype "passive"))
      (node (ref "R3") (pin "1") (pinfunction "E_1") (pintype "passive"))
    )
    (net (code "97") (name "VCC") (class "Default")
      (node (ref "C11") (pin "1") (pinfunction "1_1") (pintype "passive"))
      (node (ref "C13") (pin "1") (pinfunction "1_1") (pintype "passive"))
      (node (ref "C19") (pin "1") (pinfunction "1_1") (pintype "passive"))
      (node (ref "C42") (pin "1") (pinfunction "1_1") (pintype "passive"))
      (node (ref "C43") (pin "1") (pinfunction "1_1") (pintype "passive"))
      (node (ref "C45") (pin "1") (pinfunction "1_1") (pintype "passive"))
      (node (ref "C46") (pin "+") (pinfunction "+_+") (pintype "passive"))
      (node (ref "C47") (pin "1") (pinfunction "1_1") (pintype "passive"))
      (node (ref "C50") (pin "1") (pinfunction "1_1") (pintype "passive"))
      (node (ref "C53") (pin "+") (pinfunction "+_+") (pintype "passive"))
      (node (ref "C6") (pin "1") (pinfunction "1_1") (pintype "passive"))
      (node (ref "IC10") (pin "1") (pinfunction "VCC_1") (pintype "input"))
      (node (ref "IC11") (pin "OUT") (pinfunction "OUT_OUT") (pintype "passive"))
      (node (ref "IC2") (pin "8") (pinfunction "V+_8") (pintype "power_in"))
      (node (ref "IC3") (pin "11") (pinfunction "V+_11") (pintype "power_in"))
      (node (ref "IC4") (pin "4") (pinfunction "V+_4") (pintype "power_in"))
      (node (ref "IC5") (pin "11") (pinfunction "V+_11") (pintype "power_in"))
      (node (ref "IC7") (pin "1") (pinfunction "VDD_1") (pintype "power_in"))
      (node (ref "IC8") (pin "16") (pinfunction "V+_16") (pintype "power_in"))
      (node (ref "IC9") (pin "8") (pinfunction "V+_8") (pintype "power_in"))
      (node (ref "J5") (pin "2") (pinfunction "2_2") (pintype "passive"))
    )
    (net (code "98") (name "VEE") (class "Default")
      (node (ref "C17") (pin "2") (pinfunction "2_2") (pintype "passive"))
      (node (ref "C18") (pin "2") (pinfunction "2_2") (pintype "passive"))
      (node (ref "C22") (pin "2") (pinfunction "2_2") (pintype "passive"))
      (node (ref "C24") (pin "-") (pinfunction "-_-") (pintype "passive"))
      (node (ref "C33") (pin "2") (pinfunction "2_2") (pintype "passive"))
      (node (ref "C36") (pin "2") (pinfunction "2_2") (pintype "passive"))
      (node (ref "C8") (pin "2") (pinfunction "2_2") (pintype "passive"))
      (node (ref "IC2") (pin "4") (pinfunction "V-_4") (pintype "power_in"))
      (node (ref "IC3") (pin "6") (pinfunction "V-_6") (pintype "power_in"))
      (node (ref "IC4") (pin "11") (pinfunction "V-_11") (pintype "power_in"))
      (node (ref "IC5") (pin "6") (pinfunction "V-_6") (pintype "power_in"))
      (node (ref "IC6") (pin "OUT") (pinfunction "OUT_OUT") (pintype "passive"))
      (node (ref "IC8") (pin "9") (pinfunction "V-_9") (pintype "power_in"))
      (node (ref "IC9") (pin "4") (pinfunction "V-_4") (pintype "power_in"))
      (node (ref "R11") (pin "2") (pinfunction "2_2") (pintype "passive"))
      (node (ref "R14") (pin "1") (pinfunction "1_1") (pintype "passive"))
      (node (ref "R19") (pin "2") (pinfunction "2_2") (pintype "passive"))
      (node (ref "R30") (pin "1") (pinfunction "1_1") (pintype "passive"))
      (node (ref "R36") (pin "2") (pinfunction "2_2") (pintype "passive"))
      (node (ref "R4") (pin "1") (pinfunction "1_1") (pintype "passive"))
      (node (ref "R58") (pin "1") (pinfunction "1_1") (pintype "passive"))
    )
    (net (code "99") (name "unconnected-(IC1-Pad1)") (class "Default")
      (node (ref "IC1") (pin "1") (pinfunction "1_1") (pintype "passive"))
    )
    (net (code "100") (name "unconnected-(IC1-Pad6)") (class "Default")
      (node (ref "IC1") (pin "6") (pinfunction "6_6") (pintype "passive"))
    )
    (net (code "101") (name "unconnected-(IC3A-B-Pad7)") (class "Default")
      (node (ref "IC3") (pin "7") (pinfunction "B_7") (pintype "passive"))
    )
    (net (code "102") (name "unconnected-(IC3A-E-Pad8)") (class "Default")
      (node (ref "IC3") (pin "8") (pinfunction "E_8") (pintype "passive"))
    )
    (net (code "103") (name "unconnected-(IC3C-I_DIODE-Pad2)") (class "Default")
      (node (ref "IC3") (pin "2") (pinfunction "I_DIODE_2") (pintype "input"))
    )
    (net (code "104") (name "unconnected-(IC3D-I_DIODE-Pad15)") (class "Default")
      (node (ref "IC3") (pin "15") (pinfunction "I_DIODE_15") (pintype "input"))
    )
    (net (code "105") (name "unconnected-(IC5C-I_DIODE-Pad2)") (class "Default")
      (node (ref "IC5") (pin "2") (pinfunction "I_DIODE_2") (pintype "input"))
    )
    (net (code "106") (name "unconnected-(IC5D-I_DIODE-Pad15)") (class "Default")
      (node (ref "IC5") (pin "15") (pinfunction "I_DIODE_15") (pintype "input"))
    )
    (net (code "107") (name "unconnected-(IC8E-MODE-Pad1)") (class "Default")
      (node (ref "IC8") (pin "1") (pinfunction "MODE_1") (pintype "input"))
    )
    (net (code "108") (name "unconnected-(IC10-CLK_O-Pad5)") (class "Default")
      (node (ref "IC10") (pin "5") (pinfunction "CLK_O_5") (pintype "input"))
    )
    (net (code "109") (name "unconnected-(J1-Pad2)") (class "Default")
      (node (ref "J1") (pin "2") (pinfunction "2_2") (pintype "passive"))
    )
    (net (code "110") (name "unconnected-(J3-PadTN)") (class "Default")
      (node (ref "J3") (pin "TN") (pinfunction "TN_TN") (pintype "passive"))
    )
    (net (code "111") (name "unconnected-(J6-Pad1)") (class "Default")
      (node (ref "J6") (pin "1") (pinfunction "1_1") (pintype "passive"))
    )
    (net (code "112") (name "unconnected-(J6-Pad2)") (class "Default")
      (node (ref "J6") (pin "2") (pinfunction "2_2") (pintype "passive"))
    )
    (net (code "113") (name "unconnected-(J6-Pad5)") (class "Default")
      (node (ref "J6") (pin "5") (pinfunction "5_5") (pintype "passive"))
    )
  )
)
